# MBC1_1-4.net
KiCad netlist of a schematic drawn in EAGLE
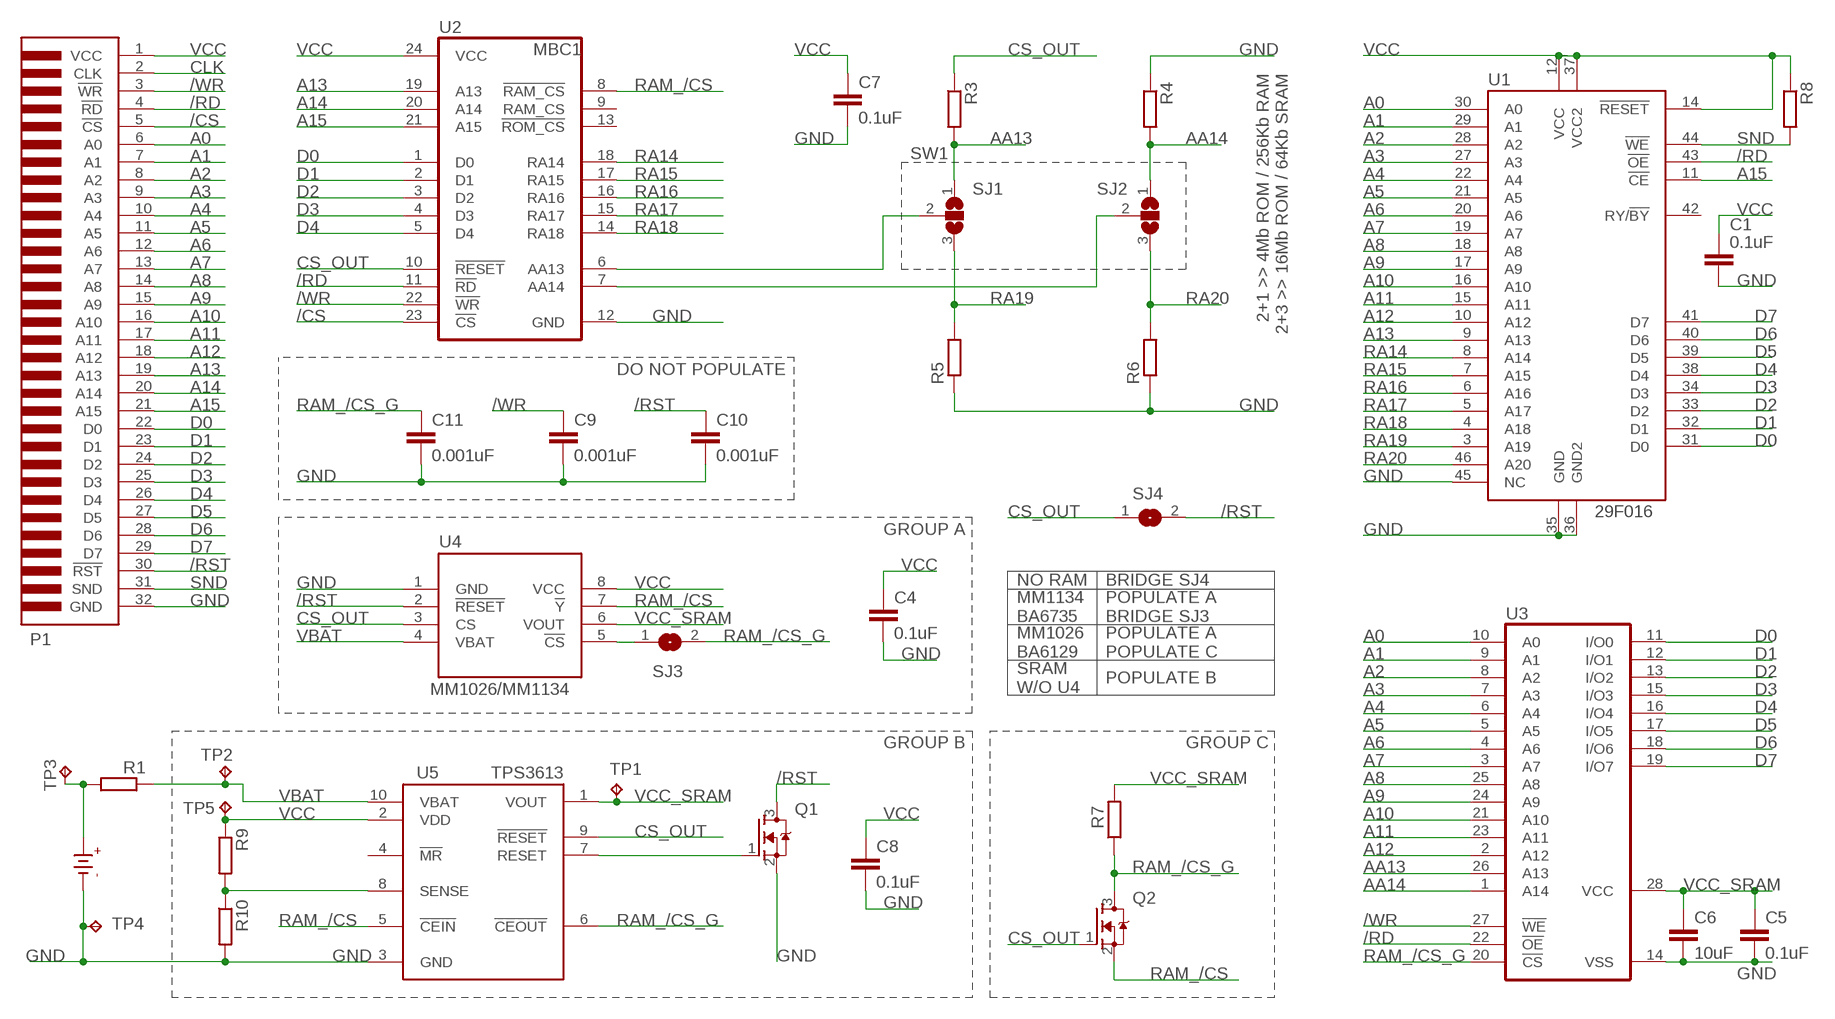
[diagram p0: schematic, sheet 1]

(export (version "E")
  (design (tool "Eeschema 10.0.6"))
  (components
    (comp (ref "B1")
      (value "CR2025")
      (footprint "eagle-import:CR2025")
      (libsource (lib "eagle-import") (part "CR2025"))
    )
    (comp (ref "C1")
      (value "0.1uF")
      (footprint "eagle-import:C0603")
      (libsource (lib "eagle-import") (part "C-EUC0603"))
    )
    (comp (ref "C4")
      (value "0.1uF")
      (footprint "eagle-import:C0603")
      (libsource (lib "eagle-import") (part "C-EUC0603"))
    )
    (comp (ref "C5")
      (value "0.1uF")
      (footprint "eagle-import:C0603")
      (libsource (lib "eagle-import") (part "C-EUC0603"))
    )
    (comp (ref "C6")
      (value "10uF")
      (footprint "eagle-import:C0603")
      (libsource (lib "eagle-import") (part "C-EUC0603"))
    )
    (comp (ref "C7")
      (value "0.1uF")
      (footprint "eagle-import:C0603")
      (libsource (lib "eagle-import") (part "C-EUC0603"))
    )
    (comp (ref "C8")
      (value "0.1uF")
      (footprint "eagle-import:C0603")
      (libsource (lib "eagle-import") (part "C-EUC0603"))
    )
    (comp (ref "C9")
      (value "0.001uF")
      (footprint "eagle-import:C0603")
      (libsource (lib "eagle-import") (part "C-EUC0603"))
    )
    (comp (ref "C10")
      (value "0.001uF")
      (footprint "eagle-import:C0603")
      (libsource (lib "eagle-import") (part "C-EUC0603"))
    )
    (comp (ref "C11")
      (value "0.001uF")
      (footprint "eagle-import:C0603")
      (libsource (lib "eagle-import") (part "C-EUC0603"))
    )
    (comp (ref "P1")
      (value "GBC_CARTTAB")
      (footprint "eagle-import:GBC_CART_TABBED")
      (libsource (lib "eagle-import") (part "GBC_CARTTAB"))
    )
    (comp (ref "Q1")
      (value "2N7002")
      (footprint "eagle-import:SOT23")
      (libsource (lib "eagle-import") (part "MOSFET-NREFLOW"))
    )
    (comp (ref "Q2")
      (value "2N7002")
      (footprint "eagle-import:SOT23")
      (libsource (lib "eagle-import") (part "MOSFET-NREFLOW"))
    )
    (comp (ref "R1")
      (value "RR0603")
      (footprint "eagle-import:R0603")
      (libsource (lib "eagle-import") (part "RR0603"))
    )
    (comp (ref "R3")
      (value "RR0603")
      (footprint "eagle-import:R0603")
      (libsource (lib "eagle-import") (part "RR0603"))
    )
    (comp (ref "R4")
      (value "RR0603")
      (footprint "eagle-import:R0603")
      (libsource (lib "eagle-import") (part "RR0603"))
    )
    (comp (ref "R5")
      (value "RR0603")
      (footprint "eagle-import:R0603")
      (libsource (lib "eagle-import") (part "RR0603"))
    )
    (comp (ref "R6")
      (value "RR0603")
      (footprint "eagle-import:R0603")
      (libsource (lib "eagle-import") (part "RR0603"))
    )
    (comp (ref "R7")
      (value "RR0603")
      (footprint "eagle-import:R0603")
      (libsource (lib "eagle-import") (part "RR0603"))
    )
    (comp (ref "R8")
      (value "RR0603")
      (footprint "eagle-import:R0603")
      (libsource (lib "eagle-import") (part "RR0603"))
    )
    (comp (ref "R9")
      (value "RR0603")
      (footprint "eagle-import:R0603")
      (libsource (lib "eagle-import") (part "RR0603"))
    )
    (comp (ref "R10")
      (value "RR0603")
      (footprint "eagle-import:R0603")
      (libsource (lib "eagle-import") (part "RR0603"))
    )
    (comp (ref "SJ1")
      (value "SJ2W")
      (footprint "eagle-import:SJ_2")
      (libsource (lib "eagle-import") (part "SJ2W"))
    )
    (comp (ref "SJ2")
      (value "SJ2W")
      (footprint "eagle-import:SJ_2")
      (libsource (lib "eagle-import") (part "SJ2W"))
    )
    (comp (ref "SJ3") (value "SJ") (footprint "eagle-import:SJ") (libsource (lib "eagle-import") (part "SJ")))
    (comp (ref "SJ4") (value "SJ") (footprint "eagle-import:SJ") (libsource (lib "eagle-import") (part "SJ")))
    (comp (ref "TP1")
      (value "TPB1,27")
      (footprint "eagle-import:B1,27")
      (libsource (lib "eagle-import") (part "TPB1,27"))
    )
    (comp (ref "TP2")
      (value "TPB1,27")
      (footprint "eagle-import:B1,27")
      (libsource (lib "eagle-import") (part "TPB1,27"))
    )
    (comp (ref "TP3")
      (value "TPB1,27")
      (footprint "eagle-import:B1,27")
      (libsource (lib "eagle-import") (part "TPB1,27"))
    )
    (comp (ref "TP4")
      (value "TPB1,27")
      (footprint "eagle-import:B1,27")
      (libsource (lib "eagle-import") (part "TPB1,27"))
    )
    (comp (ref "TP5")
      (value "TPB1,27")
      (footprint "eagle-import:B1,27")
      (libsource (lib "eagle-import") (part "TPB1,27"))
    )
    (comp (ref "U1")
      (value "29F016")
      (footprint "eagle-import:TSOP-48")
      (libsource (lib "eagle-import") (part "29F016"))
    )
    (comp (ref "U2")
      (value "MBC1")
      (footprint "eagle-import:SOP-24")
      (libsource (lib "eagle-import") (part "MBC1"))
    )
    (comp (ref "U3")
      (value "62256_SRAM")
      (footprint "eagle-import:SOP-28L")
      (fields (field (name "MPN") "CY62256VNLL-70SNXI"))
      (libsource (lib "eagle-import") (part "62256_SRAM"))
    )
    (comp (ref "U4")
      (value "MM1134")
      (footprint "eagle-import:SOIC-8")
      (libsource (lib "eagle-import") (part "MM1134"))
    )
    (comp (ref "U5")
      (value "TPS3613")
      (footprint "eagle-import:MSOP-10")
      (libsource (lib "eagle-import") (part "TPS3613"))
    )
  )
  (nets
    (net (code "1") (name "/A0") (class "Default")
      (node (ref "P1") (pin "6") (pinfunction "A0_6") (pintype "output"))
      (node (ref "U1") (pin "30") (pinfunction "A0_30") (pintype "input"))
      (node (ref "U3") (pin "10") (pinfunction "A0_10") (pintype "input"))
    )
    (net (code "2") (name "/A1") (class "Default")
      (node (ref "P1") (pin "7") (pinfunction "A1_7") (pintype "output"))
      (node (ref "U1") (pin "29") (pinfunction "A1_29") (pintype "input"))
      (node (ref "U3") (pin "9") (pinfunction "A1_9") (pintype "input"))
    )
    (net (code "3") (name "/A2") (class "Default")
      (node (ref "P1") (pin "8") (pinfunction "A2_8") (pintype "output"))
      (node (ref "U1") (pin "28") (pinfunction "A2_28") (pintype "input"))
      (node (ref "U3") (pin "8") (pinfunction "A2_8") (pintype "input"))
    )
    (net (code "4") (name "/A3") (class "Default")
      (node (ref "P1") (pin "9") (pinfunction "A3_9") (pintype "output"))
      (node (ref "U1") (pin "27") (pinfunction "A3_27") (pintype "input"))
      (node (ref "U3") (pin "7") (pinfunction "A3_7") (pintype "input"))
    )
    (net (code "5") (name "/A4") (class "Default")
      (node (ref "P1") (pin "10") (pinfunction "A4_10") (pintype "output"))
      (node (ref "U1") (pin "22") (pinfunction "A4_22") (pintype "input"))
      (node (ref "U3") (pin "6") (pinfunction "A4_6") (pintype "input"))
    )
    (net (code "6") (name "/A5") (class "Default")
      (node (ref "P1") (pin "11") (pinfunction "A5_11") (pintype "output"))
      (node (ref "U1") (pin "21") (pinfunction "A5_21") (pintype "input"))
      (node (ref "U3") (pin "5") (pinfunction "A5_5") (pintype "input"))
    )
    (net (code "7") (name "/A6") (class "Default")
      (node (ref "P1") (pin "12") (pinfunction "A6_12") (pintype "output"))
      (node (ref "U1") (pin "20") (pinfunction "A6_20") (pintype "input"))
      (node (ref "U3") (pin "4") (pinfunction "A6_4") (pintype "input"))
    )
    (net (code "8") (name "/A7") (class "Default")
      (node (ref "P1") (pin "13") (pinfunction "A7_13") (pintype "output"))
      (node (ref "U1") (pin "19") (pinfunction "A7_19") (pintype "input"))
      (node (ref "U3") (pin "3") (pinfunction "A7_3") (pintype "input"))
    )
    (net (code "9") (name "/A8") (class "Default")
      (node (ref "P1") (pin "14") (pinfunction "A8_14") (pintype "output"))
      (node (ref "U1") (pin "18") (pinfunction "A8_18") (pintype "input"))
      (node (ref "U3") (pin "25") (pinfunction "A8_25") (pintype "input"))
    )
    (net (code "10") (name "/A9") (class "Default")
      (node (ref "P1") (pin "15") (pinfunction "A9_15") (pintype "output"))
      (node (ref "U1") (pin "17") (pinfunction "A9_17") (pintype "input"))
      (node (ref "U3") (pin "24") (pinfunction "A9_24") (pintype "input"))
    )
    (net (code "11") (name "/A10") (class "Default")
      (node (ref "P1") (pin "16") (pinfunction "A10_16") (pintype "output"))
      (node (ref "U1") (pin "16") (pinfunction "A10_16") (pintype "input"))
      (node (ref "U3") (pin "21") (pinfunction "A10_21") (pintype "input"))
    )
    (net (code "12") (name "/A11") (class "Default")
      (node (ref "P1") (pin "17") (pinfunction "A11_17") (pintype "output"))
      (node (ref "U1") (pin "15") (pinfunction "A11_15") (pintype "input"))
      (node (ref "U3") (pin "23") (pinfunction "A11_23") (pintype "input"))
    )
    (net (code "13") (name "/A12") (class "Default")
      (node (ref "P1") (pin "18") (pinfunction "A12_18") (pintype "output"))
      (node (ref "U1") (pin "10") (pinfunction "A12_10") (pintype "input"))
      (node (ref "U3") (pin "2") (pinfunction "A12_2") (pintype "input"))
    )
    (net (code "14") (name "/A13") (class "Default")
      (node (ref "P1") (pin "19") (pinfunction "A13_19") (pintype "output"))
      (node (ref "U1") (pin "9") (pinfunction "A13_9") (pintype "input"))
      (node (ref "U2") (pin "19") (pinfunction "A13_19") (pintype "input"))
    )
    (net (code "15") (name "/A14") (class "Default")
      (node (ref "P1") (pin "20") (pinfunction "A14_20") (pintype "output"))
      (node (ref "U2") (pin "20") (pinfunction "A14_20") (pintype "input"))
    )
    (net (code "16") (name "/A15") (class "Default")
      (node (ref "P1") (pin "21") (pinfunction "A15_21") (pintype "output"))
      (node (ref "U1") (pin "11") (pinfunction "~{CE}_11") (pintype "input"))
      (node (ref "U2") (pin "21") (pinfunction "A15_21") (pintype "input"))
    )
    (net (code "17") (name "/AA13") (class "Default")
      (node (ref "R3") (pin "2") (pinfunction "2_2") (pintype "passive"))
      (node (ref "SJ1") (pin "1") (pinfunction "1_1") (pintype "passive"))
      (node (ref "U3") (pin "26") (pinfunction "A13_26") (pintype "input"))
    )
    (net (code "18") (name "/AA14") (class "Default")
      (node (ref "R4") (pin "2") (pinfunction "2_2") (pintype "passive"))
      (node (ref "SJ2") (pin "1") (pinfunction "1_1") (pintype "passive"))
      (node (ref "U3") (pin "1") (pinfunction "A14_1") (pintype "input"))
    )
    (net (code "19") (name "/CLK") (class "Default")
      (node (ref "P1") (pin "2") (pinfunction "CLK_2") (pintype "output"))
    )
    (net (code "20") (name "/CS_OUT") (class "Default")
      (node (ref "Q2") (pin "1") (pinfunction "G_1") (pintype "bidirectional"))
      (node (ref "R3") (pin "1") (pinfunction "1_1") (pintype "passive"))
      (node (ref "SJ4") (pin "1") (pinfunction "1_1") (pintype "passive"))
      (node (ref "U2") (pin "10") (pinfunction "~{RESET}_10") (pintype "input"))
      (node (ref "U4") (pin "3") (pinfunction "CS_3") (pintype "output"))
      (node (ref "U5") (pin "9") (pinfunction "~{RESET}_9") (pintype "output"))
    )
    (net (code "21") (name "/D0") (class "Default")
      (node (ref "P1") (pin "22") (pinfunction "D0_22") (pintype "bidirectional"))
      (node (ref "U1") (pin "31") (pinfunction "D0_31") (pintype "bidirectional"))
      (node (ref "U2") (pin "1") (pinfunction "D0_1") (pintype "input"))
      (node (ref "U3") (pin "11") (pinfunction "I/O0_11") (pintype "bidirectional"))
    )
    (net (code "22") (name "/D1") (class "Default")
      (node (ref "P1") (pin "23") (pinfunction "D1_23") (pintype "bidirectional"))
      (node (ref "U1") (pin "32") (pinfunction "D1_32") (pintype "bidirectional"))
      (node (ref "U2") (pin "2") (pinfunction "D1_2") (pintype "input"))
      (node (ref "U3") (pin "12") (pinfunction "I/O1_12") (pintype "bidirectional"))
    )
    (net (code "23") (name "/D2") (class "Default")
      (node (ref "P1") (pin "24") (pinfunction "D2_24") (pintype "bidirectional"))
      (node (ref "U1") (pin "33") (pinfunction "D2_33") (pintype "bidirectional"))
      (node (ref "U2") (pin "3") (pinfunction "D2_3") (pintype "input"))
      (node (ref "U3") (pin "13") (pinfunction "I/O2_13") (pintype "bidirectional"))
    )
    (net (code "24") (name "/D3") (class "Default")
      (node (ref "P1") (pin "25") (pinfunction "D3_25") (pintype "bidirectional"))
      (node (ref "U1") (pin "34") (pinfunction "D3_34") (pintype "bidirectional"))
      (node (ref "U2") (pin "4") (pinfunction "D3_4") (pintype "input"))
      (node (ref "U3") (pin "15") (pinfunction "I/O3_15") (pintype "bidirectional"))
    )
    (net (code "25") (name "/D4") (class "Default")
      (node (ref "P1") (pin "26") (pinfunction "D4_26") (pintype "bidirectional"))
      (node (ref "U1") (pin "38") (pinfunction "D4_38") (pintype "bidirectional"))
      (node (ref "U2") (pin "5") (pinfunction "D4_5") (pintype "input"))
      (node (ref "U3") (pin "16") (pinfunction "I/O4_16") (pintype "bidirectional"))
    )
    (net (code "26") (name "/D5") (class "Default")
      (node (ref "P1") (pin "27") (pinfunction "D5_27") (pintype "bidirectional"))
      (node (ref "U1") (pin "39") (pinfunction "D5_39") (pintype "bidirectional"))
      (node (ref "U3") (pin "17") (pinfunction "I/O5_17") (pintype "bidirectional"))
    )
    (net (code "27") (name "/D6") (class "Default")
      (node (ref "P1") (pin "28") (pinfunction "D6_28") (pintype "bidirectional"))
      (node (ref "U1") (pin "40") (pinfunction "D6_40") (pintype "bidirectional"))
      (node (ref "U3") (pin "18") (pinfunction "I/O6_18") (pintype "bidirectional"))
    )
    (net (code "28") (name "/D7") (class "Default")
      (node (ref "P1") (pin "29") (pinfunction "D7_29") (pintype "bidirectional"))
      (node (ref "U1") (pin "41") (pinfunction "D7_41") (pintype "bidirectional"))
      (node (ref "U3") (pin "19") (pinfunction "I/O7_19") (pintype "bidirectional"))
    )
    (net (code "29") (name "/GND") (class "Default")
      (node (ref "B1") (pin "-") (pinfunction "-_-") (pintype "power_in"))
      (node (ref "C1") (pin "2") (pinfunction "2_2") (pintype "passive"))
      (node (ref "C10") (pin "2") (pinfunction "2_2") (pintype "passive"))
      (node (ref "C11") (pin "2") (pinfunction "2_2") (pintype "passive"))
      (node (ref "C4") (pin "2") (pinfunction "2_2") (pintype "passive"))
      (node (ref "C5") (pin "2") (pinfunction "2_2") (pintype "passive"))
      (node (ref "C6") (pin "2") (pinfunction "2_2") (pintype "passive"))
      (node (ref "C7") (pin "2") (pinfunction "2_2") (pintype "passive"))
      (node (ref "C8") (pin "2") (pinfunction "2_2") (pintype "passive"))
      (node (ref "C9") (pin "2") (pinfunction "2_2") (pintype "passive"))
      (node (ref "P1") (pin "32") (pinfunction "GND_32") (pintype "power_in"))
      (node (ref "Q1") (pin "2") (pinfunction "S_2") (pintype "bidirectional"))
      (node (ref "R10") (pin "2") (pinfunction "2_2") (pintype "passive"))
      (node (ref "R4") (pin "1") (pinfunction "1_1") (pintype "passive"))
      (node (ref "R5") (pin "1") (pinfunction "1_1") (pintype "passive"))
      (node (ref "R6") (pin "1") (pinfunction "1_1") (pintype "passive"))
      (node (ref "TP4") (pin "TP") (pinfunction "TP_TP") (pintype "input"))
      (node (ref "U1") (pin "35") (pinfunction "GND_35") (pintype "power_in"))
      (node (ref "U1") (pin "36") (pinfunction "GND2_36") (pintype "power_in"))
      (node (ref "U1") (pin "45") (pinfunction "NC_45") (pintype "input"))
      (node (ref "U2") (pin "12") (pinfunction "GND_12") (pintype "power_in"))
      (node (ref "U3") (pin "14") (pinfunction "VSS_14") (pintype "power_in"))
      (node (ref "U4") (pin "1") (pinfunction "GND_1") (pintype "power_in"))
      (node (ref "U5") (pin "3") (pinfunction "GND_3") (pintype "power_in"))
    )
    (net (code "30") (name "/RA14") (class "Default")
      (node (ref "U1") (pin "8") (pinfunction "A14_8") (pintype "input"))
      (node (ref "U2") (pin "18") (pinfunction "RA14_18") (pintype "output"))
    )
    (net (code "31") (name "/RA15") (class "Default")
      (node (ref "U1") (pin "7") (pinfunction "A15_7") (pintype "input"))
      (node (ref "U2") (pin "17") (pinfunction "RA15_17") (pintype "output"))
    )
    (net (code "32") (name "/RA16") (class "Default")
      (node (ref "U1") (pin "6") (pinfunction "A16_6") (pintype "input"))
      (node (ref "U2") (pin "16") (pinfunction "RA16_16") (pintype "output"))
    )
    (net (code "33") (name "/RA17") (class "Default")
      (node (ref "U1") (pin "5") (pinfunction "A17_5") (pintype "input"))
      (node (ref "U2") (pin "15") (pinfunction "RA17_15") (pintype "output"))
    )
    (net (code "34") (name "/RA18") (class "Default")
      (node (ref "U1") (pin "4") (pinfunction "A18_4") (pintype "input"))
      (node (ref "U2") (pin "14") (pinfunction "RA18_14") (pintype "output"))
    )
    (net (code "35") (name "/RA19") (class "Default")
      (node (ref "R5") (pin "2") (pinfunction "2_2") (pintype "passive"))
      (node (ref "SJ1") (pin "3") (pinfunction "3_3") (pintype "passive"))
      (node (ref "U1") (pin "3") (pinfunction "A19_3") (pintype "input"))
    )
    (net (code "36") (name "/RA20") (class "Default")
      (node (ref "R6") (pin "2") (pinfunction "2_2") (pintype "passive"))
      (node (ref "SJ2") (pin "3") (pinfunction "3_3") (pintype "passive"))
      (node (ref "U1") (pin "46") (pinfunction "A20_46") (pintype "input"))
    )
    (net (code "37") (name "/RAM_{slash}CS") (class "Default")
      (node (ref "Q2") (pin "2") (pinfunction "S_2") (pintype "bidirectional"))
      (node (ref "U2") (pin "8") (pinfunction "~{RAM_CS}_8") (pintype "output"))
      (node (ref "U4") (pin "7") (pinfunction "~{Y}_7") (pintype "input"))
      (node (ref "U5") (pin "5") (pinfunction "~{CEIN}_5") (pintype "input"))
    )
    (net (code "38") (name "/RAM_{slash}CS_G") (class "Default")
      (node (ref "C11") (pin "1") (pinfunction "1_1") (pintype "passive"))
      (node (ref "Q2") (pin "3") (pinfunction "D_3") (pintype "bidirectional"))
      (node (ref "R7") (pin "1") (pinfunction "1_1") (pintype "passive"))
      (node (ref "SJ3") (pin "2") (pinfunction "2_2") (pintype "passive"))
      (node (ref "U3") (pin "20") (pinfunction "~{CS}_20") (pintype "input"))
      (node (ref "U5") (pin "6") (pinfunction "~{CEOUT}_6") (pintype "output"))
    )
    (net (code "39") (name "/SND") (class "Default")
      (node (ref "P1") (pin "31") (pinfunction "SND_31") (pintype "bidirectional"))
      (node (ref "R8") (pin "2") (pinfunction "2_2") (pintype "passive"))
      (node (ref "U1") (pin "44") (pinfunction "~{WE}_44") (pintype "input"))
    )
    (net (code "40") (name "/VBAT") (class "Default")
      (node (ref "R1") (pin "1") (pinfunction "1_1") (pintype "passive"))
      (node (ref "TP2") (pin "TP") (pinfunction "TP_TP") (pintype "input"))
      (node (ref "U4") (pin "4") (pinfunction "VBAT_4") (pintype "power_in"))
      (node (ref "U5") (pin "10") (pinfunction "VBAT_10") (pintype "power_in"))
    )
    (net (code "41") (name "/VCC") (class "Default")
      (node (ref "C1") (pin "1") (pinfunction "1_1") (pintype "passive"))
      (node (ref "C4") (pin "1") (pinfunction "1_1") (pintype "passive"))
      (node (ref "C7") (pin "1") (pinfunction "1_1") (pintype "passive"))
      (node (ref "C8") (pin "1") (pinfunction "1_1") (pintype "passive"))
      (node (ref "P1") (pin "1") (pinfunction "VCC_1") (pintype "power_in"))
      (node (ref "R8") (pin "1") (pinfunction "1_1") (pintype "passive"))
      (node (ref "R9") (pin "1") (pinfunction "1_1") (pintype "passive"))
      (node (ref "TP5") (pin "TP") (pinfunction "TP_TP") (pintype "input"))
      (node (ref "U1") (pin "12") (pinfunction "VCC_12") (pintype "power_in"))
      (node (ref "U1") (pin "14") (pinfunction "~{RESET}_14") (pintype "input"))
      (node (ref "U1") (pin "37") (pinfunction "VCC2_37") (pintype "power_in"))
      (node (ref "U2") (pin "24") (pinfunction "VCC_24") (pintype "power_in"))
      (node (ref "U4") (pin "8") (pinfunction "VCC_8") (pintype "power_in"))
      (node (ref "U5") (pin "2") (pinfunction "VDD_2") (pintype "power_in"))
    )
    (net (code "42") (name "/VCC_SRAM") (class "Default")
      (node (ref "C5") (pin "1") (pinfunction "1_1") (pintype "passive"))
      (node (ref "C6") (pin "1") (pinfunction "1_1") (pintype "passive"))
      (node (ref "R7") (pin "2") (pinfunction "2_2") (pintype "passive"))
      (node (ref "TP1") (pin "TP") (pinfunction "TP_TP") (pintype "input"))
      (node (ref "U3") (pin "28") (pinfunction "VCC_28") (pintype "power_in"))
      (node (ref "U4") (pin "6") (pinfunction "VOUT_6") (pintype "power_in"))
      (node (ref "U5") (pin "1") (pinfunction "VOUT_1") (pintype "power_in"))
    )
    (net (code "43") (name "/{slash}CS") (class "Default")
      (node (ref "P1") (pin "5") (pinfunction "~{CS}_5") (pintype "output"))
      (node (ref "U2") (pin "23") (pinfunction "~{CS}_23") (pintype "input"))
    )
    (net (code "44") (name "/{slash}RD") (class "Default")
      (node (ref "P1") (pin "4") (pinfunction "~{RD}_4") (pintype "output"))
      (node (ref "U1") (pin "43") (pinfunction "~{OE}_43") (pintype "input"))
      (node (ref "U2") (pin "11") (pinfunction "~{RD}_11") (pintype "input"))
      (node (ref "U3") (pin "22") (pinfunction "~{OE}_22") (pintype "input"))
    )
    (net (code "45") (name "/{slash}RST") (class "Default")
      (node (ref "C10") (pin "1") (pinfunction "1_1") (pintype "passive"))
      (node (ref "P1") (pin "30") (pinfunction "~{RST}_30") (pintype "bidirectional"))
      (node (ref "Q1") (pin "3") (pinfunction "D_3") (pintype "bidirectional"))
      (node (ref "SJ4") (pin "2") (pinfunction "2_2") (pintype "passive"))
      (node (ref "U4") (pin "2") (pinfunction "~{RESET}_2") (pintype "input"))
    )
    (net (code "46") (name "/{slash}WR") (class "Default")
      (node (ref "C9") (pin "1") (pinfunction "1_1") (pintype "passive"))
      (node (ref "P1") (pin "3") (pinfunction "~{WR}_3") (pintype "output"))
      (node (ref "U2") (pin "22") (pinfunction "~{WR}_22") (pintype "input"))
      (node (ref "U3") (pin "27") (pinfunction "~{WE}_27") (pintype "input"))
    )
    (net (code "47") (name "Net-(B1-Pad+)") (class "Default")
      (node (ref "B1") (pin "+") (pinfunction "+_+") (pintype "power_in"))
      (node (ref "R1") (pin "2") (pinfunction "2_2") (pintype "passive"))
      (node (ref "TP3") (pin "TP") (pinfunction "TP_TP") (pintype "input"))
    )
    (net (code "48") (name "Net-(Q1-G)") (class "Default")
      (node (ref "Q1") (pin "1") (pinfunction "G_1") (pintype "bidirectional"))
      (node (ref "U5") (pin "7") (pinfunction "RESET_7") (pintype "output"))
    )
    (net (code "49") (name "Net-(U2-AA13)") (class "Default")
      (node (ref "SJ1") (pin "2") (pinfunction "2_2") (pintype "passive"))
      (node (ref "U2") (pin "6") (pinfunction "AA13_6") (pintype "output"))
    )
    (net (code "50") (name "Net-(U2-AA14)") (class "Default")
      (node (ref "SJ2") (pin "2") (pinfunction "2_2") (pintype "passive"))
      (node (ref "U2") (pin "7") (pinfunction "AA14_7") (pintype "output"))
    )
    (net (code "51") (name "Net-(U4-~{CS})") (class "Default")
      (node (ref "SJ3") (pin "1") (pinfunction "1_1") (pintype "passive"))
      (node (ref "U4") (pin "5") (pinfunction "~{CS}_5") (pintype "output"))
    )
    (net (code "52") (name "Net-(U5-SENSE)") (class "Default")
      (node (ref "R10") (pin "1") (pinfunction "1_1") (pintype "passive"))
      (node (ref "R9") (pin "2") (pinfunction "2_2") (pintype "passive"))
      (node (ref "U5") (pin "8") (pinfunction "SENSE_8") (pintype "input"))
    )
    (net (code "53") (name "unconnected-(U1-RY{slash}~{BY}-Pad42)") (class "Default")
      (node (ref "U1") (pin "42") (pinfunction "RY/~{BY}_42") (pintype "output"))
    )
    (net (code "54") (name "unconnected-(U2-RAM_CS-Pad9)") (class "Default")
      (node (ref "U2") (pin "9") (pinfunction "RAM_CS_9") (pintype "output"))
    )
    (net (code "55") (name "unconnected-(U2-~{ROM_CS}-Pad13)") (class "Default")
      (node (ref "U2") (pin "13") (pinfunction "~{ROM_CS}_13") (pintype "output"))
    )
    (net (code "56") (name "unconnected-(U5-~{MR}-Pad4)") (class "Default")
      (node (ref "U5") (pin "4") (pinfunction "~{MR}_4") (pintype "input"))
    )
  )
)
